# neck.net
KiCad netlist of a schematic drawn in Altium Designer
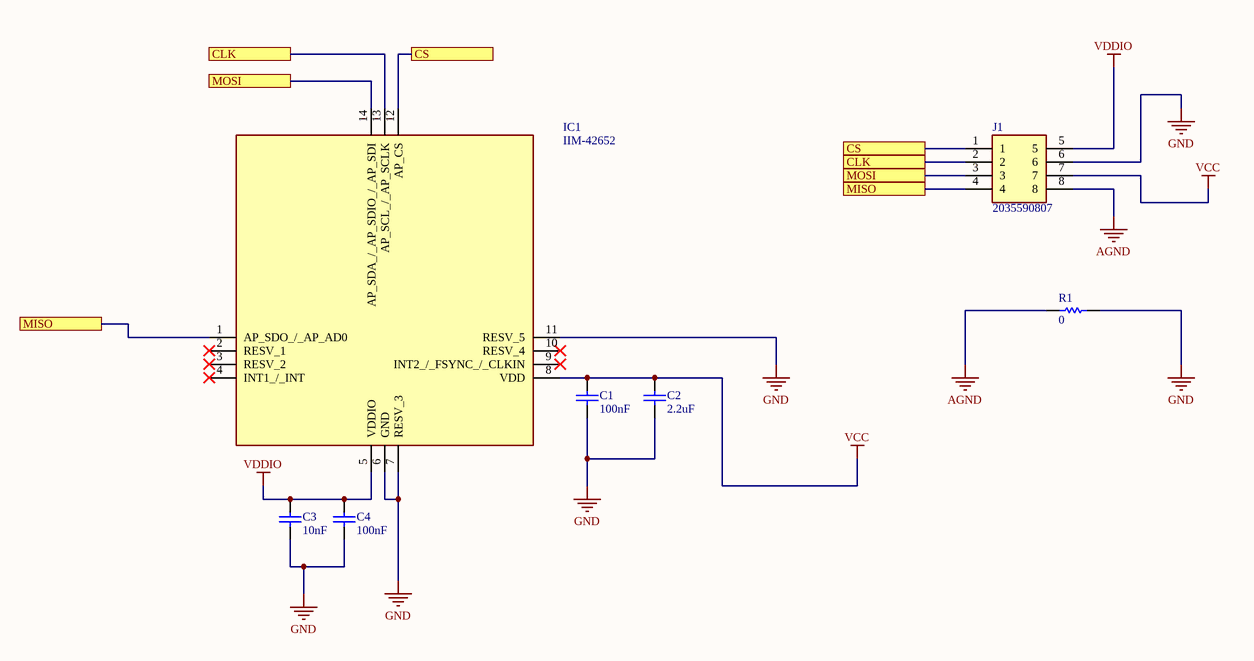
[diagram p0: neck.SchDoc]

(export (version "E")
  (design (tool "Eeschema 10.0.6"))
  (components
    (comp (ref "C1")
      (value "100nF")
      (footprint "CAP_1005")
      (description "1005(Metric) smd ceramic capacitor")
      (libsource (lib "smd componenets") (part "CAP 1005"))
    )
    (comp (ref "C2")
      (value "2.2uF")
      (footprint "CAP_1005")
      (description "1005(Metric) smd ceramic capacitor")
      (libsource (lib "smd componenets") (part "CAP 1005"))
    )
    (comp (ref "C3")
      (value "10nF")
      (footprint "CAP_1005")
      (description "1005(Metric) smd ceramic capacitor")
      (libsource (lib "smd componenets") (part "CAP 1005"))
    )
    (comp (ref "C4")
      (value "100nF")
      (footprint "CAP_1005")
      (description "1005(Metric) smd ceramic capacitor")
      (libsource (lib "smd componenets") (part "CAP 1005"))
    )
    (comp (ref "IC1")
      (value "IIM-42652")
      (footprint "SamacSys:IIM42652")
      (description "Integrated Circuit")
      (fields (field (name "MOUSER PART NUMBER") "410-IIM-42652"))
      (libsource (lib "*") (part "IIM-42652"))
    )
    (comp (ref "J1")
      (value "2035590807")
      (footprint "SamacSys:2035590807")
      (description "Connector")
      (libsource (lib "*") (part "2035590807"))
    )
    (comp (ref "R1")
      (value "0")
      (footprint "RES_1005")
      (description "1005(Metric) smd resistor")
      (libsource (lib "smd componenets") (part "RES 1005"))
    )
  )
  (nets
    (net (code "1") (name "/CLK") (class "Default")
      (node (ref "IC1") (pin "13") (pinfunction "AP_SCL_/_AP_SCLK_13") (pintype "passive"))
      (node (ref "J1") (pin "2") (pinfunction "2_2") (pintype "passive"))
    )
    (net (code "2") (name "/CS") (class "Default")
      (node (ref "IC1") (pin "12") (pinfunction "AP_CS_12") (pintype "passive"))
      (node (ref "J1") (pin "1") (pinfunction "1_1") (pintype "passive"))
    )
    (net (code "3") (name "/MISO") (class "Default")
      (node (ref "IC1") (pin "1") (pinfunction "AP_SDO_/_AP_AD0_1") (pintype "passive"))
      (node (ref "J1") (pin "4") (pinfunction "4_4") (pintype "passive"))
    )
    (net (code "4") (name "/MOSI") (class "Default")
      (node (ref "IC1") (pin "14") (pinfunction "AP_SDA_/_AP_SDIO_/_AP_SDI_14") (pintype "passive"))
      (node (ref "J1") (pin "3") (pinfunction "3_3") (pintype "passive"))
    )
    (net (code "5") (name "AGND") (class "Default")
      (node (ref "J1") (pin "8") (pinfunction "8_8") (pintype "passive"))
      (node (ref "R1") (pin "1") (pinfunction "1_1") (pintype "passive"))
    )
    (net (code "6") (name "GND") (class "Default")
      (node (ref "C1") (pin "1") (pinfunction "1_1") (pintype "passive"))
      (node (ref "C2") (pin "1") (pinfunction "1_1") (pintype "passive"))
      (node (ref "C3") (pin "1") (pinfunction "1_1") (pintype "passive"))
      (node (ref "C4") (pin "1") (pinfunction "1_1") (pintype "passive"))
      (node (ref "IC1") (pin "11") (pinfunction "RESV_5_11") (pintype "passive"))
      (node (ref "IC1") (pin "6") (pinfunction "GND_6") (pintype "passive"))
      (node (ref "IC1") (pin "7") (pinfunction "RESV_3_7") (pintype "passive"))
      (node (ref "J1") (pin "6") (pinfunction "6_6") (pintype "passive"))
      (node (ref "R1") (pin "2") (pinfunction "2_2") (pintype "passive"))
    )
    (net (code "7") (name "VCC") (class "Default")
      (node (ref "C1") (pin "2") (pinfunction "2_2") (pintype "passive"))
      (node (ref "C2") (pin "2") (pinfunction "2_2") (pintype "passive"))
      (node (ref "IC1") (pin "8") (pinfunction "VDD_8") (pintype "passive"))
      (node (ref "J1") (pin "7") (pinfunction "7_7") (pintype "passive"))
    )
    (net (code "8") (name "VDDIO") (class "Default")
      (node (ref "C3") (pin "2") (pinfunction "2_2") (pintype "passive"))
      (node (ref "C4") (pin "2") (pinfunction "2_2") (pintype "passive"))
      (node (ref "IC1") (pin "5") (pinfunction "VDDIO_5") (pintype "passive"))
      (node (ref "J1") (pin "5") (pinfunction "5_5") (pintype "passive"))
    )
    (net (code "9") (name "unconnected-(IC1-INT1_{slash}_INT-Pad4)") (class "Default")
      (node (ref "IC1") (pin "4") (pinfunction "INT1_/_INT_4") (pintype "passive+no_connect"))
    )
    (net (code "10") (name "unconnected-(IC1-INT2_{slash}_FSYNC_{slash}_CLKIN-Pad9)") (class "Default")
      (node (ref "IC1") (pin "9") (pinfunction "INT2_/_FSYNC_/_CLKIN_9") (pintype "passive+no_connect"))
    )
    (net (code "11") (name "unconnected-(IC1-RESV_1-Pad2)") (class "Default")
      (node (ref "IC1") (pin "2") (pinfunction "RESV_1_2") (pintype "passive+no_connect"))
    )
    (net (code "12") (name "unconnected-(IC1-RESV_2-Pad3)") (class "Default")
      (node (ref "IC1") (pin "3") (pinfunction "RESV_2_3") (pintype "passive+no_connect"))
    )
    (net (code "13") (name "unconnected-(IC1-RESV_4-Pad10)") (class "Default")
      (node (ref "IC1") (pin "10") (pinfunction "RESV_4_10") (pintype "passive+no_connect"))
    )
  )
)
